# vdiv.net
KiCad netlist of a schematic drawn in Altium Designer
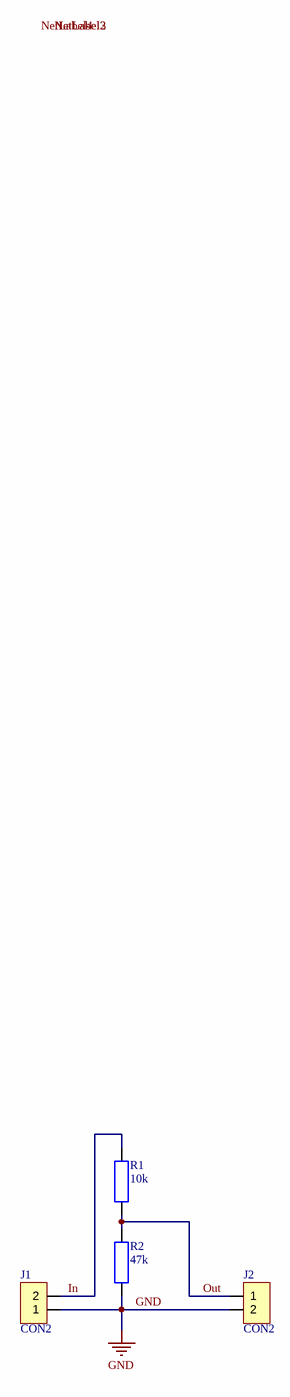
[diagram p0: vdiv.SchDoc]

(export (version "E")
  (design (tool "Eeschema 10.0.6"))
  (components
    (comp (ref "J1") (value "CON2") (footprint "POWER2") (libsource (lib "DEVICE_HSLU") (part "CON2")))
    (comp (ref "J2") (value "CON2") (footprint "POWER2") (libsource (lib "") (part "CON2_1")))
    (comp (ref "R1")
      (value "10k")
      (footprint "0805")
      (description "Normaler Widerstand")
      (libsource (lib "DEVICE_HSLU") (part "R?"))
    )
    (comp (ref "R2")
      (value "47k")
      (footprint "0805")
      (description "Normaler Widerstand")
      (libsource (lib "DEVICE_HSLU") (part "R?"))
    )
  )
  (nets
    (net (code "1") (name "/In") (class "Default")
      (node (ref "J1") (pin "2") (pinfunction "2_2") (pintype "passive"))
      (node (ref "R1") (pin "2") (pintype "passive"))
    )
    (net (code "4") (name "/Out") (class "Default")
      (node (ref "J2") (pin "1") (pinfunction "1_1") (pintype "passive"))
      (node (ref "R1") (pin "1") (pintype "passive"))
      (node (ref "R2") (pin "2") (pintype "passive"))
    )
    (net (code "5") (name "GND") (class "Default")
      (node (ref "J1") (pin "1") (pinfunction "1_1") (pintype "passive"))
      (node (ref "J2") (pin "2") (pinfunction "2_2") (pintype "passive"))
      (node (ref "R2") (pin "1") (pintype "passive"))
    )
  )
)
